# main_pwr.net
KiCad netlist of a schematic drawn in Altium Designer
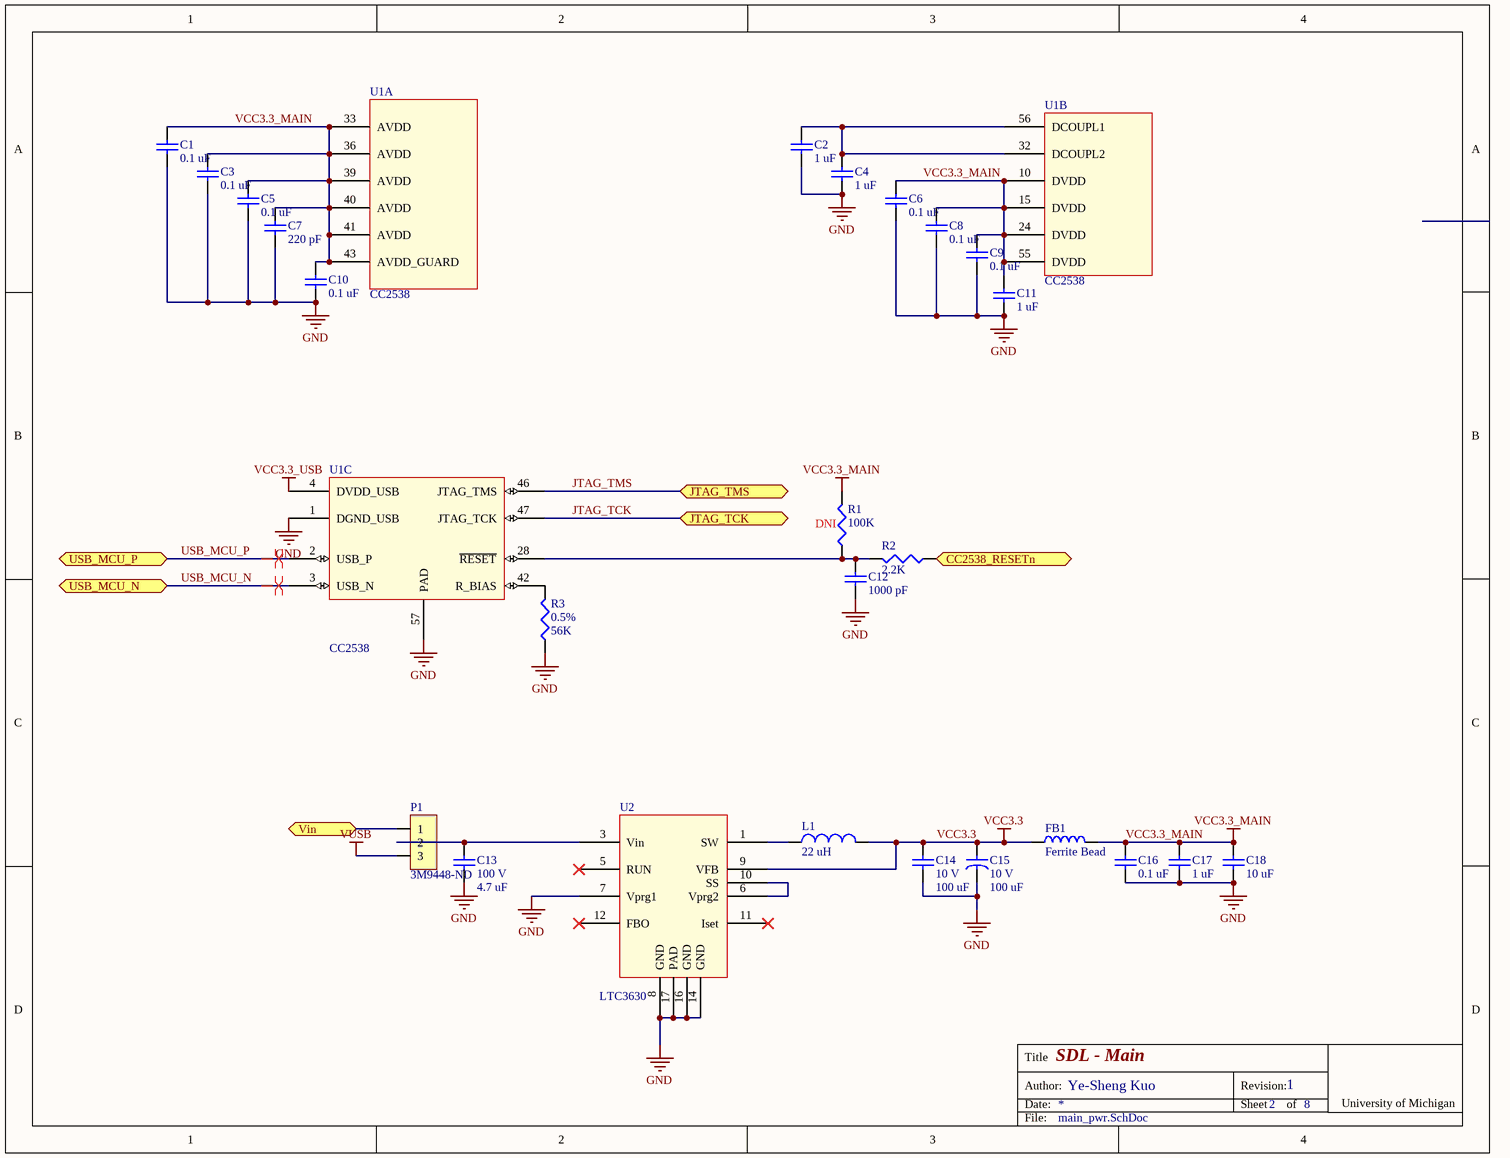
[diagram p0: main_pwr.SchDoc]

(export (version "E")
  (design (tool "Eeschema 10.0.6"))
  (components
    (comp (ref "C1")
      (value "0.1 uF")
      (footprint "0402")
      (description "Ceramic capacitor, 0.1u, 0402 package")
      (fields (field (name "TOLERANCE") "10%") (field (name "Comment") "Ceramic capacitor"))
      (libsource (lib "rlc") (part "C_0.1u_0402_ceramic"))
    )
    (comp (ref "C2")
      (value "1 uF")
      (footprint "0402")
      (description "Ceramic capacitor, 1 uF, 0402 package")
      (fields (field (name "TOLERANCE") "10%") (field (name "Comment") "Ceramic capacitor"))
      (libsource (lib "rlc") (part "C_1u_0402_ceramic"))
    )
    (comp (ref "C3")
      (value "0.1 uF")
      (footprint "0402")
      (description "Ceramic capacitor, 0.1u, 0402 package")
      (fields (field (name "TOLERANCE") "10%") (field (name "Comment") "Ceramic capacitor"))
      (libsource (lib "rlc") (part "C_0.1u_0402_ceramic"))
    )
    (comp (ref "C4")
      (value "1 uF")
      (footprint "0402")
      (description "Ceramic capacitor, 1 uF, 0402 package")
      (fields (field (name "TOLERANCE") "10%") (field (name "Comment") "Ceramic capacitor"))
      (libsource (lib "rlc") (part "C_1u_0402_ceramic"))
    )
    (comp (ref "C5")
      (value "0.1 uF")
      (footprint "0402")
      (description "Ceramic capacitor, 0.1u, 0402 package")
      (fields (field (name "TOLERANCE") "10%") (field (name "Comment") "Ceramic capacitor"))
      (libsource (lib "rlc") (part "C_0.1u_0402_ceramic"))
    )
    (comp (ref "C6")
      (value "0.1 uF")
      (footprint "0402")
      (description "Ceramic capacitor, 0.1u, 0402 package")
      (fields (field (name "TOLERANCE") "10%") (field (name "Comment") "Ceramic capacitor"))
      (libsource (lib "rlc") (part "C_0.1u_0402_ceramic"))
    )
    (comp (ref "C7")
      (value "220 pF")
      (footprint "0402")
      (description "Ceramic capacitor, 220 pF, 0402 package")
      (fields (field (name "TOLERANCE") "10%") (field (name "Comment") "Ceramic capacitor"))
      (libsource (lib "rlc") (part "C_220p_0402_ceramic"))
    )
    (comp (ref "C8")
      (value "0.1 uF")
      (footprint "0402")
      (description "Ceramic capacitor, 0.1u, 0402 package")
      (fields (field (name "TOLERANCE") "10%") (field (name "Comment") "Ceramic capacitor"))
      (libsource (lib "rlc") (part "C_0.1u_0402_ceramic"))
    )
    (comp (ref "C9")
      (value "0.1 uF")
      (footprint "0402")
      (description "Ceramic capacitor, 0.1u, 0402 package")
      (fields (field (name "TOLERANCE") "10%") (field (name "Comment") "Ceramic capacitor"))
      (libsource (lib "rlc") (part "C_0.1u_0402_ceramic"))
    )
    (comp (ref "C10")
      (value "0.1 uF")
      (footprint "0402")
      (description "Ceramic capacitor, 0.1u, 0402 package")
      (fields (field (name "TOLERANCE") "10%") (field (name "Comment") "Ceramic capacitor"))
      (libsource (lib "rlc") (part "C_0.1u_0402_ceramic"))
    )
    (comp (ref "C11")
      (value "1 uF")
      (footprint "0402")
      (description "Ceramic capacitor, 1 uF, 0402 package")
      (fields (field (name "TOLERANCE") "10%") (field (name "Comment") "Ceramic capacitor"))
      (libsource (lib "rlc") (part "C_1u_0402_ceramic"))
    )
    (comp (ref "C12")
      (value "1000 pF")
      (footprint "0402")
      (description "Ceramic capacitor, 1000 pF, 0402 package")
      (fields (field (name "TOLERANCE") "10%") (field (name "Comment") "Ceramic capacitor"))
      (libsource (lib "rlc") (part "C_1000p_0402_ceramic"))
    )
    (comp (ref "C13")
      (value "4.7 uF")
      (footprint "2220")
      (description "Ceramic capacitor, 4.7u, 2220 package")
      (fields
        (field (name "TOLERANCE") "20%")
        (field (name "VOLTAGE RATED") "100 V")
        (field (name "Comment") "Ceramic capacitor")
      )
      (libsource (lib "rlc") (part "C_4.7u_2220_ceramic"))
    )
    (comp (ref "C14")
      (value "100 uF")
      (footprint "1210")
      (description "Ceramic capacitor, 100u, 1210 package")
      (fields
        (field (name "TOLERANCE") "20%")
        (field (name "VOLTAGE RATED") "10 V")
        (field (name "Comment") "Ceramic capacitor")
      )
      (libsource (lib "rlc") (part "C_100u_1210_ceramic"))
    )
    (comp (ref "C15")
      (value "100 uF")
      (footprint "2917")
      (description "Tantalum capacitor, 100u, 2917 package")
      (fields
        (field (name "TOLERANCE") "10%")
        (field (name "VOLTAGE RATED") "10 V")
        (field (name "Comment") "Ceramic capacitor")
      )
      (libsource (lib "rlc") (part "C_100u_2917_tantalum"))
    )
    (comp (ref "C16")
      (value "0.1 uF")
      (footprint "0402")
      (description "Ceramic capacitor, 0.1u, 0402 package")
      (fields (field (name "TOLERANCE") "10%") (field (name "Comment") "Ceramic capacitor"))
      (libsource (lib "rlc") (part "C_0.1u_0402_ceramic"))
    )
    (comp (ref "C17")
      (value "1 uF")
      (footprint "0402")
      (description "Ceramic capacitor, 1 uF, 0402 package")
      (fields (field (name "TOLERANCE") "10%") (field (name "Comment") "Ceramic capacitor"))
      (libsource (lib "rlc") (part "C_1u_0402_ceramic"))
    )
    (comp (ref "C18")
      (value "10 uF")
      (footprint "0603")
      (description "Ceramic capacitor, 10 uF, 0603 package")
      (fields (field (name "TOLERANCE") "20%") (field (name "Comment") "Ceramic capacitor"))
      (libsource (lib "rlc") (part "C_10u_0603_ceramic"))
    )
    (comp (ref "FB1")
      (value "Ferrite Bead")
      (footprint "0402")
      (description "Ferrite Bead, 150 mA, 0402 package")
      (libsource (lib "rlc") (part "FB_150mA_0402"))
    )
    (comp (ref "L1")
      (value "22 uH")
      (footprint "SLF10145")
      (description "Inductor, 22 uH, TDK SLF10145")
      (fields (field (name "Comment") "L_22uH_SLF10145"))
      (libsource (lib "rlc") (part "L_22uH_SLF10145"))
    )
    (comp (ref "P1")
      (value "1 x 3 header")
      (footprint "1x3 header")
      (description "100 mils standard header")
      (fields (field (name "SUPPLIER PART NUMBER 1") "3M9448-ND"))
      (libsource (lib "connectors") (part "1 x 3 header"))
    )
    (comp (ref "R1")
      (value "100K")
      (footprint "0402")
      (description "Chip resistor, 100K, 0402 package")
      (fields (field (name "TOLERANCE") "1%") (field (name "POWER") "1/16 W"))
      (libsource (lib "rlc") (part "R_100K_0402"))
    )
    (comp (ref "R2")
      (value "2.2K")
      (footprint "0402")
      (description "Chip resistor, 2.2K, 0402 package")
      (fields (field (name "TOLERANCE") "1%") (field (name "POWER") "1/16 W"))
      (libsource (lib "rlc") (part "R_2.2K_0402"))
    )
    (comp (ref "R3")
      (value "56K")
      (footprint "0402")
      (description "Chip resistor, 56K, 0402 package")
      (fields
        (field (name "POWER") "1/16 W")
        (field (name "TOLERANCE") "0.5%")
        (field (name "Comment") "Chip resistor")
      )
      (libsource (lib "rlc") (part "R_56K_0402"))
    )
    (comp (ref "U1")
      (value "CC2538")
      (footprint "QFN56")
      (description "A Powerful System-On-Chip for 2.4-GHz IEEE 802.15.4, 6LoWPAN  and ZigBee Applications")
      (libsource (lib "sdl") (part "CC2538"))
    )
    (comp (ref "U2")
      (value "LTC3630")
      (footprint "MSE16(12)")
      (description "High Efficiency, 65V 500mA synchronous Step-Down Converter")
      (libsource (lib "sdl") (part "LTC3630"))
    )
  )
  (nets
    (net (code "1") (name "/CC2538_RESETn") (class "Default") (node (ref "R2") (pin "2") (pintype "passive")))
    (net (code "2") (name "/JTAG_TCK") (class "Default")
      (node (ref "U1") (pin "47") (pinfunction "JTAG_TCK_47") (pintype "bidirectional"))
    )
    (net (code "3") (name "/JTAG_TMS") (class "Default")
      (node (ref "U1") (pin "46") (pinfunction "JTAG_TMS_46") (pintype "bidirectional"))
    )
    (net (code "4") (name "/USB_MCU_N") (class "Default")
      (node (ref "U1") (pin "3") (pinfunction "USB_N_3") (pintype "bidirectional"))
    )
    (net (code "5") (name "/USB_MCU_P") (class "Default")
      (node (ref "U1") (pin "2") (pinfunction "USB_P_2") (pintype "bidirectional"))
    )
    (net (code "6") (name "/Vin") (class "Default")
      (node (ref "P1") (pin "1") (pinfunction "1_1") (pintype "passive"))
    )
    (net (code "7") (name "GND") (class "Default")
      (node (ref "C1") (pin "2") (pintype "passive"))
      (node (ref "C10") (pin "2") (pintype "passive"))
      (node (ref "C11") (pin "2") (pintype "passive"))
      (node (ref "C12") (pin "2") (pintype "passive"))
      (node (ref "C13") (pin "2") (pintype "passive"))
      (node (ref "C14") (pin "2") (pintype "passive"))
      (node (ref "C15") (pin "2") (pintype "passive"))
      (node (ref "C16") (pin "2") (pintype "passive"))
      (node (ref "C17") (pin "2") (pintype "passive"))
      (node (ref "C18") (pin "2") (pintype "passive"))
      (node (ref "C2") (pin "2") (pintype "passive"))
      (node (ref "C3") (pin "2") (pintype "passive"))
      (node (ref "C4") (pin "2") (pintype "passive"))
      (node (ref "C5") (pin "2") (pintype "passive"))
      (node (ref "C6") (pin "2") (pintype "passive"))
      (node (ref "C7") (pin "2") (pintype "passive"))
      (node (ref "C8") (pin "2") (pintype "passive"))
      (node (ref "C9") (pin "2") (pintype "passive"))
      (node (ref "R3") (pin "2") (pintype "passive"))
      (node (ref "U1") (pin "1") (pinfunction "DGND_USB_1") (pintype "power_in"))
      (node (ref "U1") (pin "57") (pinfunction "PAD_57") (pintype "power_in"))
      (node (ref "U2") (pin "14") (pinfunction "GND_14") (pintype "passive"))
      (node (ref "U2") (pin "16") (pinfunction "GND_16") (pintype "passive"))
      (node (ref "U2") (pin "17") (pinfunction "PAD_17") (pintype "passive"))
      (node (ref "U2") (pin "7") (pinfunction "Vprg1_7") (pintype "passive"))
      (node (ref "U2") (pin "8") (pinfunction "GND_8") (pintype "passive"))
    )
    (net (code "8") (name "Net-(U1B-DCOUPL1)") (class "Default")
      (node (ref "C2") (pin "1") (pintype "passive"))
      (node (ref "C4") (pin "1") (pintype "passive"))
      (node (ref "U1") (pin "32") (pinfunction "DCOUPL2_32") (pintype "power_in"))
      (node (ref "U1") (pin "56") (pinfunction "DCOUPL1_56") (pintype "power_in"))
    )
    (net (code "9") (name "Net-(U1C-R_BIAS)") (class "Default")
      (node (ref "R3") (pin "1") (pintype "passive"))
      (node (ref "U1") (pin "42") (pinfunction "R_BIAS_42") (pintype "bidirectional"))
    )
    (net (code "10") (name "Net-(U1C-~{RESET})") (class "Default")
      (node (ref "C12") (pin "1") (pintype "passive"))
      (node (ref "R1") (pin "2") (pintype "passive"))
      (node (ref "R2") (pin "1") (pintype "passive"))
      (node (ref "U1") (pin "28") (pinfunction "~{RESET}_28") (pintype "bidirectional"))
    )
    (net (code "11") (name "Net-(U2-SS)") (class "Default")
      (node (ref "U2") (pin "10") (pinfunction "SS_10") (pintype "passive"))
      (node (ref "U2") (pin "6") (pinfunction "Vprg2_6") (pintype "passive"))
    )
    (net (code "12") (name "Net-(U2-SW)") (class "Default")
      (node (ref "L1") (pin "2") (pinfunction "2_2") (pintype "passive"))
      (node (ref "U2") (pin "1") (pinfunction "SW_1") (pintype "passive"))
    )
    (net (code "13") (name "Net-(U2-Vin)") (class "Default")
      (node (ref "C13") (pin "1") (pintype "passive"))
      (node (ref "P1") (pin "2") (pinfunction "2_2") (pintype "passive"))
      (node (ref "U2") (pin "3") (pinfunction "Vin_3") (pintype "passive"))
    )
    (net (code "14") (name "VCC3.3") (class "Default")
      (node (ref "C14") (pin "1") (pintype "passive"))
      (node (ref "C15") (pin "1") (pintype "passive"))
      (node (ref "FB1") (pin "2") (pintype "passive"))
      (node (ref "L1") (pin "1") (pinfunction "1_1") (pintype "passive"))
      (node (ref "U2") (pin "9") (pinfunction "VFB_9") (pintype "passive"))
    )
    (net (code "15") (name "VCC3.3_MAIN") (class "Default")
      (node (ref "C1") (pin "1") (pintype "passive"))
      (node (ref "C10") (pin "1") (pintype "passive"))
      (node (ref "C11") (pin "1") (pintype "passive"))
      (node (ref "C16") (pin "1") (pintype "passive"))
      (node (ref "C17") (pin "1") (pintype "passive"))
      (node (ref "C18") (pin "1") (pintype "passive"))
      (node (ref "C3") (pin "1") (pintype "passive"))
      (node (ref "C5") (pin "1") (pintype "passive"))
      (node (ref "C6") (pin "1") (pintype "passive"))
      (node (ref "C7") (pin "1") (pintype "passive"))
      (node (ref "C8") (pin "1") (pintype "passive"))
      (node (ref "C9") (pin "1") (pintype "passive"))
      (node (ref "FB1") (pin "1") (pintype "passive"))
      (node (ref "R1") (pin "1") (pintype "passive"))
      (node (ref "U1") (pin "10") (pinfunction "DVDD_10") (pintype "power_in"))
      (node (ref "U1") (pin "15") (pinfunction "DVDD_15") (pintype "power_in"))
      (node (ref "U1") (pin "24") (pinfunction "DVDD_24") (pintype "power_in"))
      (node (ref "U1") (pin "33") (pinfunction "AVDD_33") (pintype "power_in"))
      (node (ref "U1") (pin "36") (pinfunction "AVDD_36") (pintype "power_in"))
      (node (ref "U1") (pin "39") (pinfunction "AVDD_39") (pintype "power_in"))
      (node (ref "U1") (pin "40") (pinfunction "AVDD_40") (pintype "power_in"))
      (node (ref "U1") (pin "41") (pinfunction "AVDD_41") (pintype "power_in"))
      (node (ref "U1") (pin "43") (pinfunction "AVDD_GUARD_43") (pintype "power_in"))
      (node (ref "U1") (pin "55") (pinfunction "DVDD_55") (pintype "power_in"))
    )
    (net (code "16") (name "VCC3.3_USB") (class "Default")
      (node (ref "U1") (pin "4") (pinfunction "DVDD_USB_4") (pintype "power_in"))
    )
    (net (code "17") (name "VUSB") (class "Default")
      (node (ref "P1") (pin "3") (pinfunction "3_3") (pintype "passive"))
    )
    (net (code "18") (name "unconnected-(U2-FBO-Pad12)") (class "Default")
      (node (ref "U2") (pin "12") (pinfunction "FBO_12") (pintype "passive+no_connect"))
    )
    (net (code "19") (name "unconnected-(U2-Iset-Pad11)") (class "Default")
      (node (ref "U2") (pin "11") (pinfunction "Iset_11") (pintype "passive+no_connect"))
    )
    (net (code "20") (name "unconnected-(U2-RUN-Pad5)") (class "Default")
      (node (ref "U2") (pin "5") (pinfunction "RUN_5") (pintype "passive+no_connect"))
    )
  )
)
